# S7CAS-PLEIADES-CARTE-MERE_P02_DDR3.net
KiCad netlist of a schematic drawn in Altium Designer
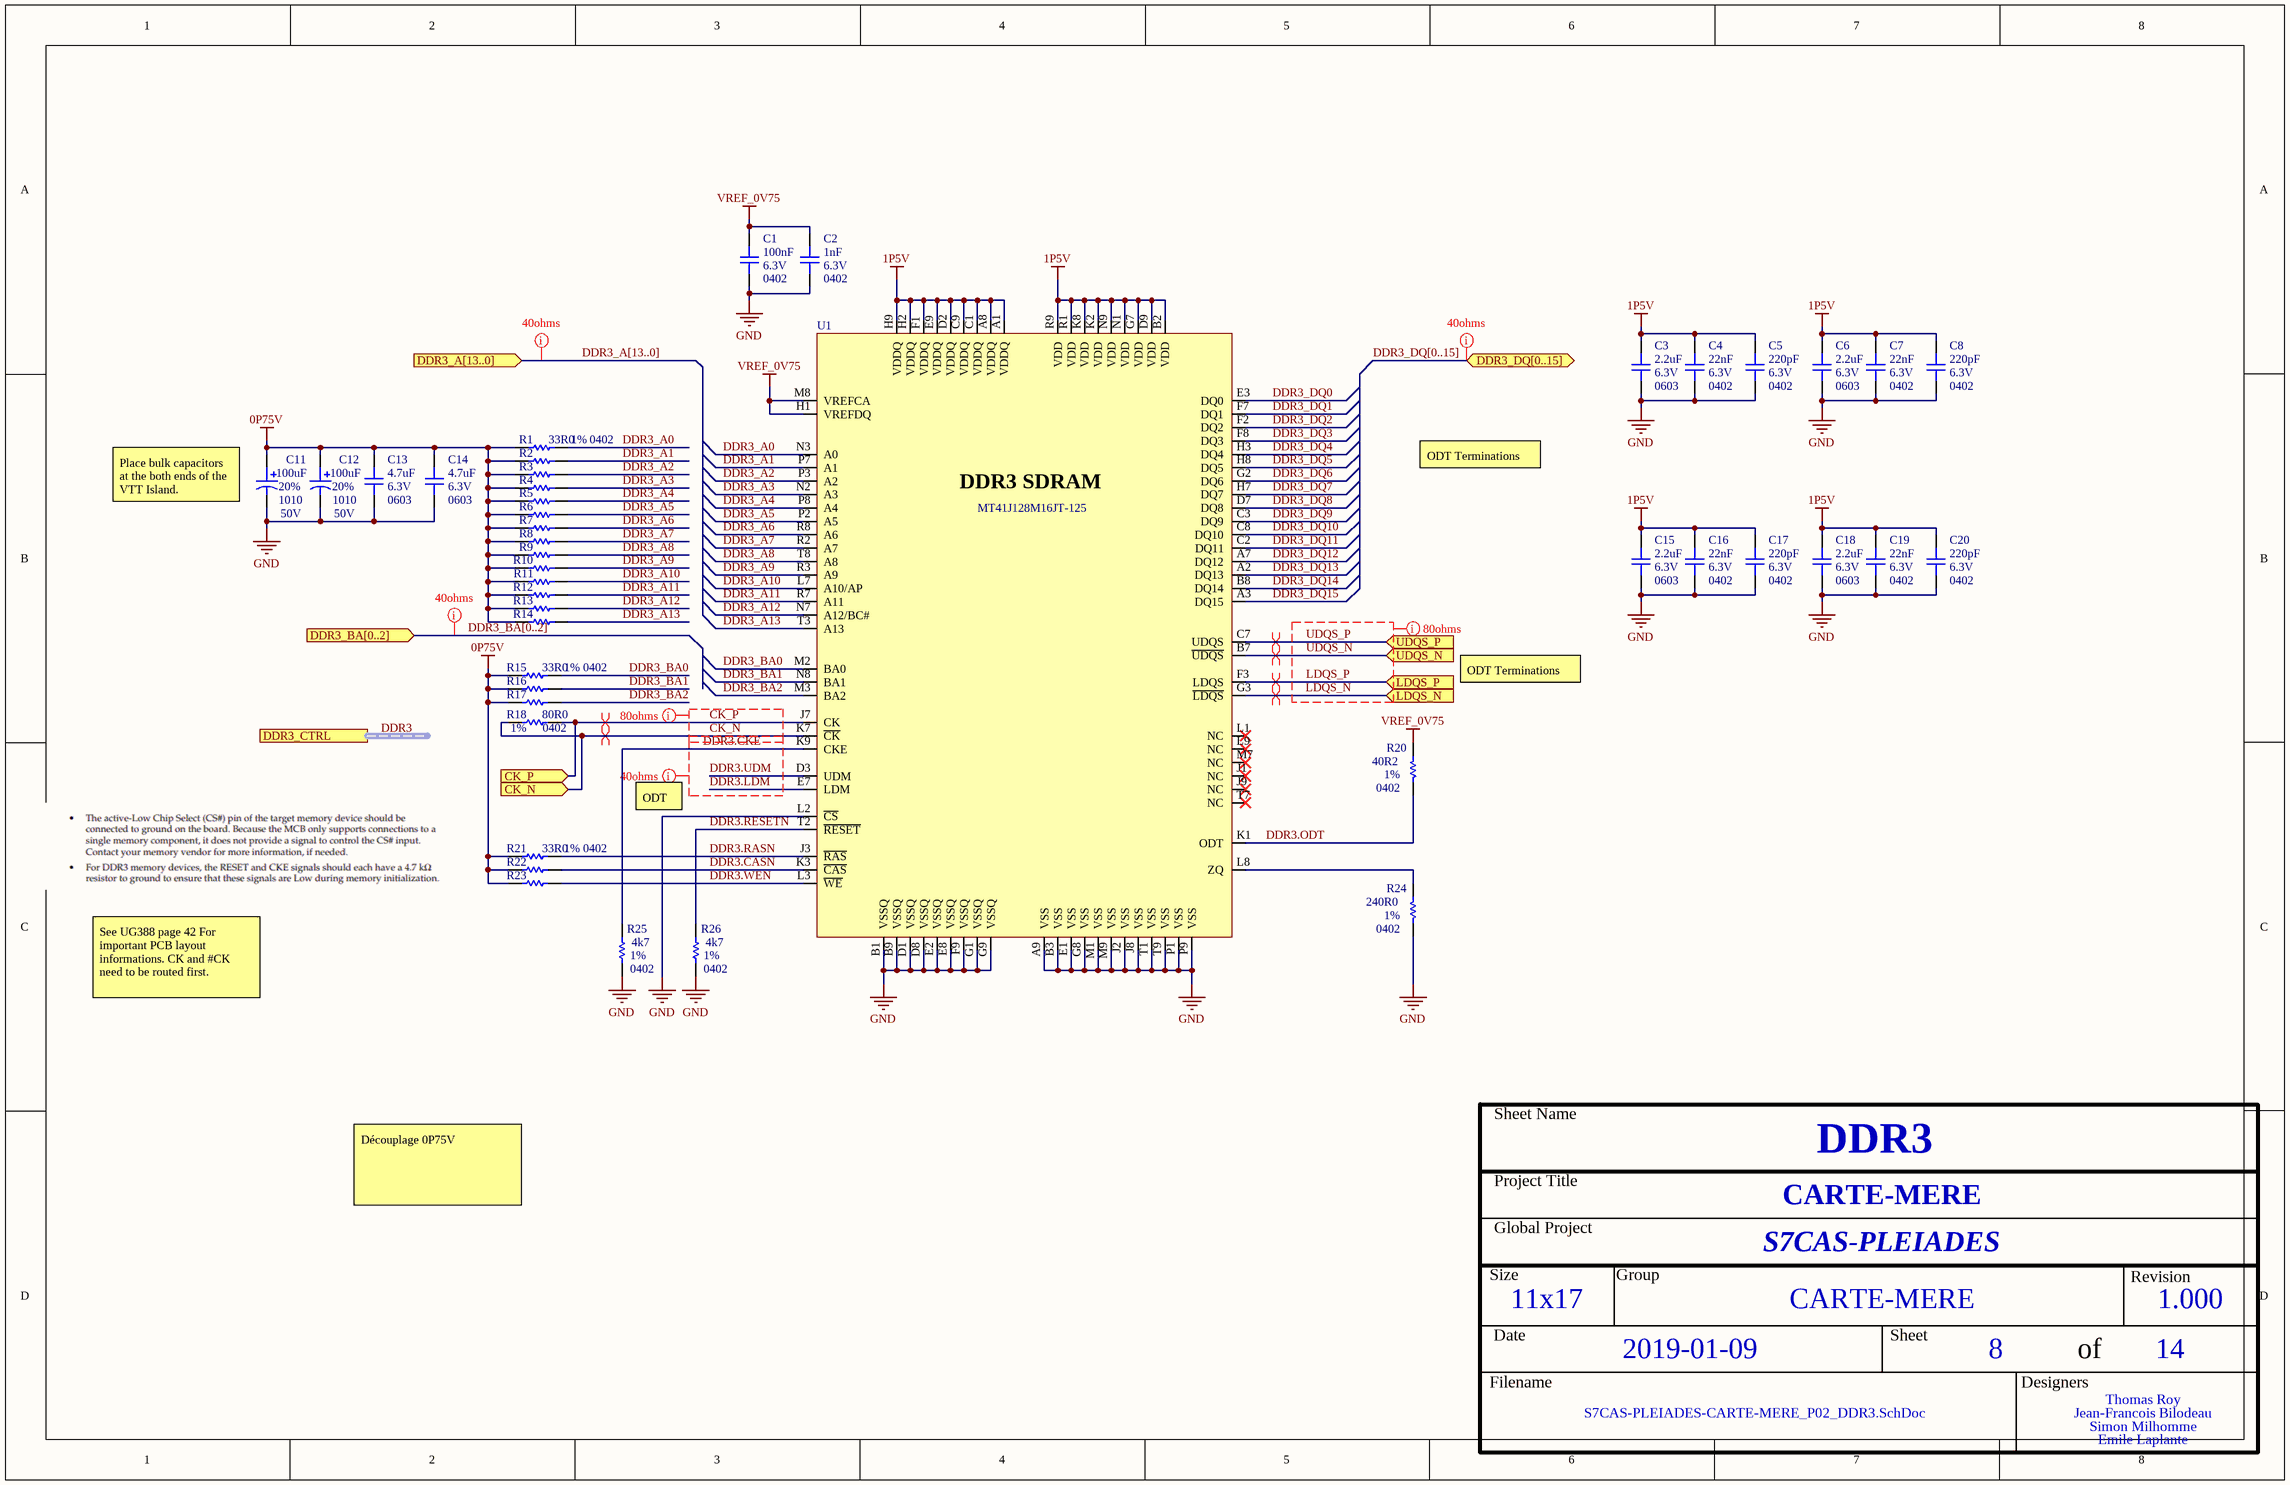
[diagram p0: S7CAS-PLEIADES-CARTE-MERE_P02_DDR3.SchDoc]

(export (version "E")
  (design (tool "Eeschema 10.0.6"))
  (components
    (comp (ref "C1")
      (value "100nF")
      (footprint "CAP_0402")
      (description "CAP - 0402")
      (fields
        (field (name "MFG") "Murata")
        (field (name "MFG PART NUMBER") "GRM022R60J104KE15")
        (field (name "VOLTAGE") "6.3V")
        (field (name "PACKAGE") "0402")
        (field (name "CREATEDBY") "Jonathan Bouchard")
      )
      (libsource (lib "S7CAS_Lib2019_REV1_00") (part "CAP - 0402"))
    )
    (comp (ref "C2")
      (value "1nF")
      (footprint "CAP_0402")
      (description "CAP - 0402")
      (fields
        (field (name "MFG") "Murata")
        (field (name "MFG PART NUMBER") "GRM022R60J104KE15")
        (field (name "VOLTAGE") "6.3V")
        (field (name "PACKAGE") "0402")
        (field (name "CREATEDBY") "Jonathan Bouchard")
      )
      (libsource (lib "S7CAS_Lib2019_REV1_00") (part "CAP - 0402"))
    )
    (comp (ref "C3")
      (value "2.2uF")
      (footprint "CAP_0603")
      (description "CAP - 0603")
      (fields
        (field (name "VOLTAGE") "6.3V")
        (field (name "PACKAGE") "0603")
        (field (name "CREATEDBY") "Jonathan Bouchard")
      )
      (libsource (lib "S7CAS_Lib2019_REV1_00") (part "CAP - 0603"))
    )
    (comp (ref "C4")
      (value "22nF")
      (footprint "CAP_0402")
      (description "CAP - 0402")
      (fields
        (field (name "MFG") "Murata")
        (field (name "MFG PART NUMBER") "GRM022R60J104KE15")
        (field (name "VOLTAGE") "6.3V")
        (field (name "PACKAGE") "0402")
        (field (name "CREATEDBY") "Jonathan Bouchard")
      )
      (libsource (lib "S7CAS_Lib2019_REV1_00") (part "CAP - 0402"))
    )
    (comp (ref "C5")
      (value "220pF")
      (footprint "CAP_0402")
      (description "CAP - 0402")
      (fields
        (field (name "MFG") "Murata")
        (field (name "MFG PART NUMBER") "GRM022R60J104KE15")
        (field (name "VOLTAGE") "6.3V")
        (field (name "PACKAGE") "0402")
        (field (name "CREATEDBY") "Jonathan Bouchard")
      )
      (libsource (lib "S7CAS_Lib2019_REV1_00") (part "CAP - 0402"))
    )
    (comp (ref "C6")
      (value "2.2uF")
      (footprint "CAP_0603")
      (description "CAP - 0603")
      (fields
        (field (name "VOLTAGE") "6.3V")
        (field (name "PACKAGE") "0603")
        (field (name "CREATEDBY") "Jonathan Bouchard")
      )
      (libsource (lib "S7CAS_Lib2019_REV1_00") (part "CAP - 0603"))
    )
    (comp (ref "C7")
      (value "22nF")
      (footprint "CAP_0402")
      (description "CAP - 0402")
      (fields
        (field (name "MFG") "Murata")
        (field (name "MFG PART NUMBER") "GRM022R60J104KE15")
        (field (name "VOLTAGE") "6.3V")
        (field (name "PACKAGE") "0402")
        (field (name "CREATEDBY") "Jonathan Bouchard")
      )
      (libsource (lib "S7CAS_Lib2019_REV1_00") (part "CAP - 0402"))
    )
    (comp (ref "C8")
      (value "220pF")
      (footprint "CAP_0402")
      (description "CAP - 0402")
      (fields
        (field (name "MFG") "Murata")
        (field (name "MFG PART NUMBER") "GRM022R60J104KE15")
        (field (name "VOLTAGE") "6.3V")
        (field (name "PACKAGE") "0402")
        (field (name "CREATEDBY") "Jonathan Bouchard")
      )
      (libsource (lib "S7CAS_Lib2019_REV1_00") (part "CAP - 0402"))
    )
    (comp (ref "C11")
      (value "100uF")
      (footprint "CAP_ALU_1010_vishay")
      (description "CAP - ALU 100uF 20% 50V - 1010")
      (fields
        (field (name "MFG") "Vishay Dale")
        (field (name "MFG PART NUMBER") "MAL215099101E3")
        (field (name "VOLTAGE") "50V")
        (field (name "PACKAGE") "1010")
        (field (name "PRECISION") "20%")
        (field (name "CREATEDBY") "Jonathan Bouchard")
      )
      (libsource (lib "S7CAS_Lib2019_REV1_00") (part "CAP_ALU_MAL215099101E3"))
    )
    (comp (ref "C12")
      (value "100uF")
      (footprint "CAP_ALU_1010_vishay")
      (description "CAP - ALU 100uF 20% 50V - 1010")
      (fields
        (field (name "MFG") "Vishay Dale")
        (field (name "MFG PART NUMBER") "MAL215099101E3")
        (field (name "VOLTAGE") "50V")
        (field (name "PACKAGE") "1010")
        (field (name "PRECISION") "20%")
        (field (name "CREATEDBY") "Jonathan Bouchard")
      )
      (libsource (lib "S7CAS_Lib2019_REV1_00") (part "CAP_ALU_MAL215099101E3"))
    )
    (comp (ref "C13")
      (value "4.7uF")
      (footprint "CAP_0603")
      (description "CAP - 0603")
      (fields
        (field (name "VOLTAGE") "6.3V")
        (field (name "PACKAGE") "0603")
        (field (name "CREATEDBY") "Jonathan Bouchard")
      )
      (libsource (lib "S7CAS_Lib2019_REV1_00") (part "CAP - 0603"))
    )
    (comp (ref "C14")
      (value "4.7uF")
      (footprint "CAP_0603")
      (description "CAP - 0603")
      (fields
        (field (name "VOLTAGE") "6.3V")
        (field (name "PACKAGE") "0603")
        (field (name "CREATEDBY") "Jonathan Bouchard")
      )
      (libsource (lib "S7CAS_Lib2019_REV1_00") (part "CAP - 0603"))
    )
    (comp (ref "C15")
      (value "2.2uF")
      (footprint "CAP_0603")
      (description "CAP - 0603")
      (fields
        (field (name "VOLTAGE") "6.3V")
        (field (name "PACKAGE") "0603")
        (field (name "CREATEDBY") "Jonathan Bouchard")
      )
      (libsource (lib "S7CAS_Lib2019_REV1_00") (part "CAP - 0603"))
    )
    (comp (ref "C16")
      (value "22nF")
      (footprint "CAP_0402")
      (description "CAP - 0402")
      (fields
        (field (name "MFG") "Murata")
        (field (name "MFG PART NUMBER") "GRM022R60J104KE15")
        (field (name "VOLTAGE") "6.3V")
        (field (name "PACKAGE") "0402")
        (field (name "CREATEDBY") "Jonathan Bouchard")
      )
      (libsource (lib "S7CAS_Lib2019_REV1_00") (part "CAP - 0402"))
    )
    (comp (ref "C17")
      (value "220pF")
      (footprint "CAP_0402")
      (description "CAP - 0402")
      (fields
        (field (name "MFG") "Murata")
        (field (name "MFG PART NUMBER") "GRM022R60J104KE15")
        (field (name "VOLTAGE") "6.3V")
        (field (name "PACKAGE") "0402")
        (field (name "CREATEDBY") "Jonathan Bouchard")
      )
      (libsource (lib "S7CAS_Lib2019_REV1_00") (part "CAP - 0402"))
    )
    (comp (ref "C18")
      (value "2.2uF")
      (footprint "CAP_0603")
      (description "CAP - 0603")
      (fields
        (field (name "VOLTAGE") "6.3V")
        (field (name "PACKAGE") "0603")
        (field (name "CREATEDBY") "Jonathan Bouchard")
      )
      (libsource (lib "S7CAS_Lib2019_REV1_00") (part "CAP - 0603"))
    )
    (comp (ref "C19")
      (value "22nF")
      (footprint "CAP_0402")
      (description "CAP - 0402")
      (fields
        (field (name "MFG") "Murata")
        (field (name "MFG PART NUMBER") "GRM022R60J104KE15")
        (field (name "VOLTAGE") "6.3V")
        (field (name "PACKAGE") "0402")
        (field (name "CREATEDBY") "Jonathan Bouchard")
      )
      (libsource (lib "S7CAS_Lib2019_REV1_00") (part "CAP - 0402"))
    )
    (comp (ref "C20")
      (value "220pF")
      (footprint "CAP_0402")
      (description "CAP - 0402")
      (fields
        (field (name "MFG") "Murata")
        (field (name "MFG PART NUMBER") "GRM022R60J104KE15")
        (field (name "VOLTAGE") "6.3V")
        (field (name "PACKAGE") "0402")
        (field (name "CREATEDBY") "Jonathan Bouchard")
      )
      (libsource (lib "S7CAS_Lib2019_REV1_00") (part "CAP - 0402"))
    )
    (comp (ref "R1")
      (value "33R0")
      (footprint "RES_0402")
      (description "RES - 0402")
      (fields
        (field (name "VOLTAGE") "50V")
        (field (name "POWER") "1/16W")
        (field (name "PACKAGE") "0402")
        (field (name "PRECISION") "1%")
        (field (name "CREATEDBY") "Jonathan Bouchard")
      )
      (libsource (lib "S7CAS_Lib2019_REV1_00") (part "RES - 0402"))
    )
    (comp (ref "R2")
      (value "RES - 0402")
      (footprint "RES_0402")
      (fields
        (field (name "VOLTAGE") "50V")
        (field (name "POWER") "1/16W")
        (field (name "CREATEDBY") "Jonathan Bouchard")
      )
      (libsource (lib "S7CAS_Lib2019_REV1_00") (part "RES - 0402"))
    )
    (comp (ref "R3")
      (value "RES - 0402")
      (footprint "RES_0402")
      (fields
        (field (name "VOLTAGE") "50V")
        (field (name "POWER") "1/16W")
        (field (name "CREATEDBY") "Jonathan Bouchard")
      )
      (libsource (lib "S7CAS_Lib2019_REV1_00") (part "RES - 0402"))
    )
    (comp (ref "R4")
      (value "RES - 0402")
      (footprint "RES_0402")
      (fields
        (field (name "VOLTAGE") "50V")
        (field (name "POWER") "1/16W")
        (field (name "CREATEDBY") "Jonathan Bouchard")
      )
      (libsource (lib "S7CAS_Lib2019_REV1_00") (part "RES - 0402"))
    )
    (comp (ref "R5")
      (value "RES - 0402")
      (footprint "RES_0402")
      (fields
        (field (name "VOLTAGE") "50V")
        (field (name "POWER") "1/16W")
        (field (name "CREATEDBY") "Jonathan Bouchard")
      )
      (libsource (lib "S7CAS_Lib2019_REV1_00") (part "RES - 0402"))
    )
    (comp (ref "R6")
      (value "RES - 0402")
      (footprint "RES_0402")
      (fields
        (field (name "VOLTAGE") "50V")
        (field (name "POWER") "1/16W")
        (field (name "CREATEDBY") "Jonathan Bouchard")
      )
      (libsource (lib "S7CAS_Lib2019_REV1_00") (part "RES - 0402"))
    )
    (comp (ref "R7")
      (value "RES - 0402")
      (footprint "RES_0402")
      (fields
        (field (name "VOLTAGE") "50V")
        (field (name "POWER") "1/16W")
        (field (name "CREATEDBY") "Jonathan Bouchard")
      )
      (libsource (lib "S7CAS_Lib2019_REV1_00") (part "RES - 0402"))
    )
    (comp (ref "R8")
      (value "RES - 0402")
      (footprint "RES_0402")
      (fields
        (field (name "VOLTAGE") "50V")
        (field (name "POWER") "1/16W")
        (field (name "CREATEDBY") "Jonathan Bouchard")
      )
      (libsource (lib "S7CAS_Lib2019_REV1_00") (part "RES - 0402"))
    )
    (comp (ref "R9")
      (value "RES - 0402")
      (footprint "RES_0402")
      (fields
        (field (name "VOLTAGE") "50V")
        (field (name "POWER") "1/16W")
        (field (name "CREATEDBY") "Jonathan Bouchard")
      )
      (libsource (lib "S7CAS_Lib2019_REV1_00") (part "RES - 0402"))
    )
    (comp (ref "R10")
      (value "RES - 0402")
      (footprint "RES_0402")
      (fields
        (field (name "VOLTAGE") "50V")
        (field (name "POWER") "1/16W")
        (field (name "CREATEDBY") "Jonathan Bouchard")
      )
      (libsource (lib "S7CAS_Lib2019_REV1_00") (part "RES - 0402"))
    )
    (comp (ref "R11")
      (value "RES - 0402")
      (footprint "RES_0402")
      (fields
        (field (name "VOLTAGE") "50V")
        (field (name "POWER") "1/16W")
        (field (name "CREATEDBY") "Jonathan Bouchard")
      )
      (libsource (lib "S7CAS_Lib2019_REV1_00") (part "RES - 0402"))
    )
    (comp (ref "R12")
      (value "RES - 0402")
      (footprint "RES_0402")
      (fields
        (field (name "VOLTAGE") "50V")
        (field (name "POWER") "1/16W")
        (field (name "CREATEDBY") "Jonathan Bouchard")
      )
      (libsource (lib "S7CAS_Lib2019_REV1_00") (part "RES - 0402"))
    )
    (comp (ref "R13")
      (value "RES - 0402")
      (footprint "RES_0402")
      (fields
        (field (name "VOLTAGE") "50V")
        (field (name "POWER") "1/16W")
        (field (name "CREATEDBY") "Jonathan Bouchard")
      )
      (libsource (lib "S7CAS_Lib2019_REV1_00") (part "RES - 0402"))
    )
    (comp (ref "R14")
      (value "RES - 0402")
      (footprint "RES_0402")
      (fields
        (field (name "VOLTAGE") "50V")
        (field (name "POWER") "1/16W")
        (field (name "CREATEDBY") "Jonathan Bouchard")
      )
      (libsource (lib "S7CAS_Lib2019_REV1_00") (part "RES - 0402"))
    )
    (comp (ref "R15")
      (value "33R0")
      (footprint "RES_0402")
      (description "RES - 0402")
      (fields
        (field (name "VOLTAGE") "50V")
        (field (name "POWER") "1/16W")
        (field (name "PACKAGE") "0402")
        (field (name "PRECISION") "1%")
        (field (name "CREATEDBY") "Jonathan Bouchard")
      )
      (libsource (lib "S7CAS_Lib2019_REV1_00") (part "RES - 0402"))
    )
    (comp (ref "R16")
      (value "RES - 0402")
      (footprint "RES_0402")
      (fields
        (field (name "VOLTAGE") "50V")
        (field (name "POWER") "1/16W")
        (field (name "CREATEDBY") "Jonathan Bouchard")
      )
      (libsource (lib "S7CAS_Lib2019_REV1_00") (part "RES - 0402"))
    )
    (comp (ref "R17")
      (value "RES - 0402")
      (footprint "RES_0402")
      (fields
        (field (name "VOLTAGE") "50V")
        (field (name "POWER") "1/16W")
        (field (name "CREATEDBY") "Jonathan Bouchard")
      )
      (libsource (lib "S7CAS_Lib2019_REV1_00") (part "RES - 0402"))
    )
    (comp (ref "R18")
      (value "80R0")
      (footprint "RES_0402")
      (description "RES - 0402")
      (fields
        (field (name "VOLTAGE") "50V")
        (field (name "POWER") "1/16W")
        (field (name "PACKAGE") "0402")
        (field (name "PRECISION") "1%")
        (field (name "CREATEDBY") "Jonathan Bouchard")
      )
      (libsource (lib "S7CAS_Lib2019_REV1_00") (part "RES - 0402"))
    )
    (comp (ref "R20")
      (value "40R2")
      (footprint "RES_0402")
      (description "RES - 0402")
      (fields
        (field (name "VOLTAGE") "50V")
        (field (name "POWER") "1/16W")
        (field (name "PACKAGE") "0402")
        (field (name "PRECISION") "1%")
        (field (name "CREATEDBY") "Jonathan Bouchard")
      )
      (libsource (lib "S7CAS_Lib2019_REV1_00") (part "RES - 0402"))
    )
    (comp (ref "R21")
      (value "33R0")
      (footprint "RES_0402")
      (description "RES - 0402")
      (fields
        (field (name "VOLTAGE") "50V")
        (field (name "POWER") "1/16W")
        (field (name "PACKAGE") "0402")
        (field (name "PRECISION") "1%")
        (field (name "CREATEDBY") "Jonathan Bouchard")
      )
      (libsource (lib "S7CAS_Lib2019_REV1_00") (part "RES - 0402"))
    )
    (comp (ref "R22")
      (value "RES - 0402")
      (footprint "RES_0402")
      (fields
        (field (name "VOLTAGE") "50V")
        (field (name "POWER") "1/16W")
        (field (name "CREATEDBY") "Jonathan Bouchard")
      )
      (libsource (lib "S7CAS_Lib2019_REV1_00") (part "RES - 0402"))
    )
    (comp (ref "R23")
      (value "RES - 0402")
      (footprint "RES_0402")
      (fields
        (field (name "VOLTAGE") "50V")
        (field (name "POWER") "1/16W")
        (field (name "CREATEDBY") "Jonathan Bouchard")
      )
      (libsource (lib "S7CAS_Lib2019_REV1_00") (part "RES - 0402"))
    )
    (comp (ref "R24")
      (value "240R0")
      (footprint "RES_0402")
      (description "RES - 0402")
      (fields
        (field (name "VOLTAGE") "50V")
        (field (name "POWER") "1/16W")
        (field (name "PACKAGE") "0402")
        (field (name "PRECISION") "1%")
        (field (name "CREATEDBY") "Jonathan Bouchard")
      )
      (libsource (lib "S7CAS_Lib2019_REV1_00") (part "RES - 0402"))
    )
    (comp (ref "R25")
      (value "4k7")
      (footprint "RES_0402")
      (description "RES - 0402")
      (fields
        (field (name "VOLTAGE") "50V")
        (field (name "POWER") "1/16W")
        (field (name "PACKAGE") "0402")
        (field (name "PRECISION") "1%")
        (field (name "CREATEDBY") "Jonathan Bouchard")
      )
      (libsource (lib "S7CAS_Lib2019_REV1_00") (part "RES - 0402"))
    )
    (comp (ref "R26")
      (value "4k7")
      (footprint "RES_0402")
      (description "RES - 0402")
      (fields
        (field (name "VOLTAGE") "50V")
        (field (name "POWER") "1/16W")
        (field (name "PACKAGE") "0402")
        (field (name "PRECISION") "1%")
        (field (name "CREATEDBY") "Jonathan Bouchard")
      )
      (libsource (lib "S7CAS_Lib2019_REV1_00") (part "RES - 0402"))
    )
    (comp (ref "U1")
      (value "MT41J128M16JT-125")
      (footprint "MEM_DDR3_MT41J128M16JT-125")
      (description "MEM - DDR3 SDRAM 2GBIT 800MHZ - TFBGA-96")
      (fields
        (field (name "VOLTAGE") "1.425 V ~ 1.575 V")
        (field (name "MFG") "Micrel")
        (field (name "CREATEDBY") "Jonathan Bouchard")
      )
      (libsource (lib "S7CAS_Lib2019_REV1_00") (part "MEM_DDR3_MT41J128M16JT-125{colon}K TR"))
    )
  )
  (nets
    (net (code "2") (name "/CK_N") (class "Default")
      (node (ref "R18") (pin "2") (pinfunction "2_2") (pintype "passive"))
      (node (ref "U1") (pin "K7") (pinfunction "CK_K7") (pintype "passive"))
    )
    (net (code "3") (name "/CK_P") (class "Default")
      (node (ref "R18") (pin "1") (pinfunction "1_1") (pintype "passive"))
      (node (ref "U1") (pin "J7") (pinfunction "CK_J7") (pintype "passive"))
    )
    (net (code "4") (name "/DDR3.CASN") (class "Default")
      (node (ref "R22") (pin "1") (pinfunction "1_1") (pintype "passive"))
      (node (ref "U1") (pin "K3") (pinfunction "CAS_K3") (pintype "passive"))
    )
    (net (code "5") (name "/DDR3.CKE") (class "Default")
      (node (ref "R25") (pin "2") (pinfunction "2_2") (pintype "passive"))
      (node (ref "U1") (pin "K9") (pinfunction "CKE_K9") (pintype "passive"))
    )
    (net (code "6") (name "/DDR3.LDM") (class "Default")
      (node (ref "U1") (pin "E7") (pinfunction "LDM_E7") (pintype "power_in"))
    )
    (net (code "7") (name "/DDR3.ODT") (class "Default")
      (node (ref "R20") (pin "1") (pinfunction "1_1") (pintype "passive"))
      (node (ref "U1") (pin "K1") (pinfunction "ODT_K1") (pintype "passive"))
    )
    (net (code "8") (name "/DDR3.RASN") (class "Default")
      (node (ref "R21") (pin "1") (pinfunction "1_1") (pintype "passive"))
      (node (ref "U1") (pin "J3") (pinfunction "RAS_J3") (pintype "passive"))
    )
    (net (code "9") (name "/DDR3.RESETN") (class "Default")
      (node (ref "R26") (pin "2") (pinfunction "2_2") (pintype "passive"))
      (node (ref "U1") (pin "T2") (pinfunction "RESET_T2") (pintype "passive"))
    )
    (net (code "10") (name "/DDR3.UDM") (class "Default")
      (node (ref "U1") (pin "D3") (pinfunction "UDM_D3") (pintype "power_in"))
    )
    (net (code "11") (name "/DDR3.WEN") (class "Default")
      (node (ref "R23") (pin "1") (pinfunction "1_1") (pintype "passive"))
      (node (ref "U1") (pin "L3") (pinfunction "WE_L3") (pintype "passive"))
    )
    (net (code "12") (name "/DDR3_A0") (class "Default")
      (node (ref "R1") (pin "1") (pinfunction "1_1") (pintype "passive"))
      (node (ref "U1") (pin "N3") (pinfunction "A0_N3") (pintype "passive"))
    )
    (net (code "13") (name "/DDR3_A1") (class "Default")
      (node (ref "R2") (pin "1") (pinfunction "1_1") (pintype "passive"))
      (node (ref "U1") (pin "P7") (pinfunction "A1_P7") (pintype "passive"))
    )
    (net (code "14") (name "/DDR3_A2") (class "Default")
      (node (ref "R3") (pin "1") (pinfunction "1_1") (pintype "passive"))
      (node (ref "U1") (pin "P3") (pinfunction "A2_P3") (pintype "passive"))
    )
    (net (code "15") (name "/DDR3_A3") (class "Default")
      (node (ref "R4") (pin "1") (pinfunction "1_1") (pintype "passive"))
      (node (ref "U1") (pin "N2") (pinfunction "A3_N2") (pintype "passive"))
    )
    (net (code "16") (name "/DDR3_A4") (class "Default")
      (node (ref "R5") (pin "1") (pinfunction "1_1") (pintype "passive"))
      (node (ref "U1") (pin "P8") (pinfunction "A4_P8") (pintype "passive"))
    )
    (net (code "17") (name "/DDR3_A5") (class "Default")
      (node (ref "R6") (pin "1") (pinfunction "1_1") (pintype "passive"))
      (node (ref "U1") (pin "P2") (pinfunction "A5_P2") (pintype "passive"))
    )
    (net (code "18") (name "/DDR3_A6") (class "Default")
      (node (ref "R7") (pin "1") (pinfunction "1_1") (pintype "passive"))
      (node (ref "U1") (pin "R8") (pinfunction "A6_R8") (pintype "passive"))
    )
    (net (code "19") (name "/DDR3_A7") (class "Default")
      (node (ref "R8") (pin "1") (pinfunction "1_1") (pintype "passive"))
      (node (ref "U1") (pin "R2") (pinfunction "A7_R2") (pintype "passive"))
    )
    (net (code "20") (name "/DDR3_A8") (class "Default")
      (node (ref "R9") (pin "1") (pinfunction "1_1") (pintype "passive"))
      (node (ref "U1") (pin "T8") (pinfunction "A8_T8") (pintype "passive"))
    )
    (net (code "21") (name "/DDR3_A9") (class "Default")
      (node (ref "R10") (pin "1") (pinfunction "1_1") (pintype "passive"))
      (node (ref "U1") (pin "R3") (pinfunction "A9_R3") (pintype "passive"))
    )
    (net (code "22") (name "/DDR3_A10") (class "Default")
      (node (ref "R11") (pin "1") (pinfunction "1_1") (pintype "passive"))
      (node (ref "U1") (pin "L7") (pinfunction "A10/AP_L7") (pintype "passive"))
    )
    (net (code "23") (name "/DDR3_A11") (class "Default")
      (node (ref "R12") (pin "1") (pinfunction "1_1") (pintype "passive"))
      (node (ref "U1") (pin "R7") (pinfunction "A11_R7") (pintype "passive"))
    )
    (net (code "24") (name "/DDR3_A12") (class "Default")
      (node (ref "R13") (pin "1") (pinfunction "1_1") (pintype "passive"))
      (node (ref "U1") (pin "N7") (pinfunction "A12/BC#_N7") (pintype "passive"))
    )
    (net (code "25") (name "/DDR3_A13") (class "Default")
      (node (ref "R14") (pin "1") (pinfunction "1_1") (pintype "passive"))
      (node (ref "U1") (pin "T3") (pinfunction "A13_T3") (pintype "passive"))
    )
    (net (code "27") (name "/DDR3_BA0") (class "Default")
      (node (ref "R15") (pin "1") (pinfunction "1_1") (pintype "passive"))
      (node (ref "U1") (pin "M2") (pinfunction "BA0_M2") (pintype "passive"))
    )
    (net (code "28") (name "/DDR3_BA1") (class "Default")
      (node (ref "R16") (pin "1") (pinfunction "1_1") (pintype "passive"))
      (node (ref "U1") (pin "N8") (pinfunction "BA1_N8") (pintype "passive"))
    )
    (net (code "29") (name "/DDR3_BA2") (class "Default")
      (node (ref "R17") (pin "1") (pinfunction "1_1") (pintype "passive"))
      (node (ref "U1") (pin "M3") (pinfunction "BA2_M3") (pintype "passive"))
    )
    (net (code "31") (name "/DDR3_DQ0") (class "Default")
      (node (ref "U1") (pin "E3") (pinfunction "DQ0_E3") (pintype "passive"))
    )
    (net (code "32") (name "/DDR3_DQ1") (class "Default")
      (node (ref "U1") (pin "F7") (pinfunction "DQ1_F7") (pintype "passive"))
    )
    (net (code "33") (name "/DDR3_DQ2") (class "Default")
      (node (ref "U1") (pin "F2") (pinfunction "DQ2_F2") (pintype "passive"))
    )
    (net (code "34") (name "/DDR3_DQ3") (class "Default")
      (node (ref "U1") (pin "F8") (pinfunction "DQ3_F8") (pintype "passive"))
    )
    (net (code "35") (name "/DDR3_DQ4") (class "Default")
      (node (ref "U1") (pin "H3") (pinfunction "DQ4_H3") (pintype "passive"))
    )
    (net (code "36") (name "/DDR3_DQ5") (class "Default")
      (node (ref "U1") (pin "H8") (pinfunction "DQ5_H8") (pintype "passive"))
    )
    (net (code "37") (name "/DDR3_DQ6") (class "Default")
      (node (ref "U1") (pin "G2") (pinfunction "DQ6_G2") (pintype "passive"))
    )
    (net (code "38") (name "/DDR3_DQ7") (class "Default")
      (node (ref "U1") (pin "H7") (pinfunction "DQ7_H7") (pintype "passive"))
    )
    (net (code "39") (name "/DDR3_DQ8") (class "Default")
      (node (ref "U1") (pin "D7") (pinfunction "DQ8_D7") (pintype "passive"))
    )
    (net (code "40") (name "/DDR3_DQ9") (class "Default")
      (node (ref "U1") (pin "C3") (pinfunction "DQ9_C3") (pintype "passive"))
    )
    (net (code "41") (name "/DDR3_DQ10") (class "Default")
      (node (ref "U1") (pin "C8") (pinfunction "DQ10_C8") (pintype "passive"))
    )
    (net (code "42") (name "/DDR3_DQ11") (class "Default")
      (node (ref "U1") (pin "C2") (pinfunction "DQ11_C2") (pintype "passive"))
    )
    (net (code "43") (name "/DDR3_DQ12") (class "Default")
      (node (ref "U1") (pin "A7") (pinfunction "DQ12_A7") (pintype "passive"))
    )
    (net (code "44") (name "/DDR3_DQ13") (class "Default")
      (node (ref "U1") (pin "A2") (pinfunction "DQ13_A2") (pintype "passive"))
    )
    (net (code "45") (name "/DDR3_DQ14") (class "Default")
      (node (ref "U1") (pin "B8") (pinfunction "DQ14_B8") (pintype "passive"))
    )
    (net (code "46") (name "/DDR3_DQ15") (class "Default")
      (node (ref "U1") (pin "A3") (pinfunction "DQ15_A3") (pintype "passive"))
    )
    (net (code "48") (name "/LDQS_N") (class "Default")
      (node (ref "U1") (pin "G3") (pinfunction "LDQS_G3") (pintype "passive"))
    )
    (net (code "49") (name "/LDQS_P") (class "Default")
      (node (ref "U1") (pin "F3") (pinfunction "LDQS_F3") (pintype "passive"))
    )
    (net (code "50") (name "/UDQS_N") (class "Default")
      (node (ref "U1") (pin "B7") (pinfunction "UDQS_B7") (pintype "passive"))
    )
    (net (code "51") (name "/UDQS_P") (class "Default")
      (node (ref "U1") (pin "C7") (pinfunction "UDQS_C7") (pintype "passive"))
    )
    (net (code "53") (name "0P75V") (class "Default")
      (node (ref "C11") (pin "1") (pinfunction "1_1") (pintype "passive"))
      (node (ref "C12") (pin "1") (pinfunction "1_1") (pintype "passive"))
      (node (ref "C13") (pin "2") (pinfunction "2_2") (pintype "passive"))
      (node (ref "C14") (pin "2") (pinfunction "2_2") (pintype "passive"))
      (node (ref "R1") (pin "2") (pinfunction "2_2") (pintype "passive"))
      (node (ref "R10") (pin "2") (pinfunction "2_2") (pintype "passive"))
      (node (ref "R11") (pin "2") (pinfunction "2_2") (pintype "passive"))
      (node (ref "R12") (pin "2") (pinfunction "2_2") (pintype "passive"))
      (node (ref "R13") (pin "2") (pinfunction "2_2") (pintype "passive"))
      (node (ref "R14") (pin "2") (pinfunction "2_2") (pintype "passive"))
      (node (ref "R15") (pin "2") (pinfunction "2_2") (pintype "passive"))
      (node (ref "R16") (pin "2") (pinfunction "2_2") (pintype "passive"))
      (node (ref "R17") (pin "2") (pinfunction "2_2") (pintype "passive"))
      (node (ref "R2") (pin "2") (pinfunction "2_2") (pintype "passive"))
      (node (ref "R21") (pin "2") (pinfunction "2_2") (pintype "passive"))
      (node (ref "R22") (pin "2") (pinfunction "2_2") (pintype "passive"))
      (node (ref "R23") (pin "2") (pinfunction "2_2") (pintype "passive"))
      (node (ref "R3") (pin "2") (pinfunction "2_2") (pintype "passive"))
      (node (ref "R4") (pin "2") (pinfunction "2_2") (pintype "passive"))
      (node (ref "R5") (pin "2") (pinfunction "2_2") (pintype "passive"))
      (node (ref "R6") (pin "2") (pinfunction "2_2") (pintype "passive"))
      (node (ref "R7") (pin "2") (pinfunction "2_2") (pintype "passive"))
      (node (ref "R8") (pin "2") (pinfunction "2_2") (pintype "passive"))
      (node (ref "R9") (pin "2") (pinfunction "2_2") (pintype "passive"))
    )
    (net (code "54") (name "1P5V") (class "Default")
      (node (ref "C15") (pin "2") (pinfunction "2_2") (pintype "passive"))
      (node (ref "C16") (pin "2") (pinfunction "2_2") (pintype "passive"))
      (node (ref "C17") (pin "2") (pinfunction "2_2") (pintype "passive"))
      (node (ref "C18") (pin "2") (pinfunction "2_2") (pintype "passive"))
      (node (ref "C19") (pin "2") (pinfunction "2_2") (pintype "passive"))
      (node (ref "C20") (pin "2") (pinfunction "2_2") (pintype "passive"))
      (node (ref "C3") (pin "2") (pinfunction "2_2") (pintype "passive"))
      (node (ref "C4") (pin "2") (pinfunction "2_2") (pintype "passive"))
      (node (ref "C5") (pin "2") (pinfunction "2_2") (pintype "passive"))
      (node (ref "C6") (pin "2") (pinfunction "2_2") (pintype "passive"))
      (node (ref "C7") (pin "2") (pinfunction "2_2") (pintype "passive"))
      (node (ref "C8") (pin "2") (pinfunction "2_2") (pintype "passive"))
      (node (ref "U1") (pin "A1") (pinfunction "VDDQ_A1") (pintype "power_in"))
      (node (ref "U1") (pin "A8") (pinfunction "VDDQ_A8") (pintype "power_in"))
      (node (ref "U1") (pin "B2") (pinfunction "VDD_B2") (pintype "power_in"))
      (node (ref "U1") (pin "C1") (pinfunction "VDDQ_C1") (pintype "power_in"))
      (node (ref "U1") (pin "C9") (pinfunction "VDDQ_C9") (pintype "power_in"))
      (node (ref "U1") (pin "D2") (pinfunction "VDDQ_D2") (pintype "power_in"))
      (node (ref "U1") (pin "D9") (pinfunction "VDD_D9") (pintype "power_in"))
      (node (ref "U1") (pin "E9") (pinfunction "VDDQ_E9") (pintype "power_in"))
      (node (ref "U1") (pin "F1") (pinfunction "VDDQ_F1") (pintype "power_in"))
      (node (ref "U1") (pin "G7") (pinfunction "VDD_G7") (pintype "power_in"))
      (node (ref "U1") (pin "H2") (pinfunction "VDDQ_H2") (pintype "power_in"))
      (node (ref "U1") (pin "H9") (pinfunction "VDDQ_H9") (pintype "power_in"))
      (node (ref "U1") (pin "K2") (pinfunction "VDD_K2") (pintype "power_in"))
      (node (ref "U1") (pin "K8") (pinfunction "VDD_K8") (pintype "power_in"))
      (node (ref "U1") (pin "N1") (pinfunction "VDD_N1") (pintype "power_in"))
      (node (ref "U1") (pin "N9") (pinfunction "VDD_N9") (pintype "power_in"))
      (node (ref "U1") (pin "R1") (pinfunction "VDD_R1") (pintype "power_in"))
      (node (ref "U1") (pin "R9") (pinfunction "VDD_R9") (pintype "power_in"))
    )
    (net (code "55") (name "GND") (class "Default")
      (node (ref "C1") (pin "1") (pinfunction "1_1") (pintype "passive"))
      (node (ref "C11") (pin "2") (pinfunction "2_2") (pintype "passive"))
      (node (ref "C12") (pin "2") (pinfunction "2_2") (pintype "passive"))
      (node (ref "C13") (pin "1") (pinfunction "1_1") (pintype "passive"))
      (node (ref "C14") (pin "1") (pinfunction "1_1") (pintype "passive"))
      (node (ref "C15") (pin "1") (pinfunction "1_1") (pintype "passive"))
      (node (ref "C16") (pin "1") (pinfunction "1_1") (pintype "passive"))
      (node (ref "C17") (pin "1") (pinfunction "1_1") (pintype "passive"))
      (node (ref "C18") (pin "1") (pinfunction "1_1") (pintype "passive"))
      (node (ref "C19") (pin "1") (pinfunction "1_1") (pintype "passive"))
      (node (ref "C2") (pin "1") (pinfunction "1_1") (pintype "passive"))
      (node (ref "C20") (pin "1") (pinfunction "1_1") (pintype "passive"))
      (node (ref "C3") (pin "1") (pinfunction "1_1") (pintype "passive"))
      (node (ref "C4") (pin "1") (pinfunction "1_1") (pintype "passive"))
      (node (ref "C5") (pin "1") (pinfunction "1_1") (pintype "passive"))
      (node (ref "C6") (pin "1") (pinfunction "1_1") (pintype "passive"))
      (node (ref "C7") (pin "1") (pinfunction "1_1") (pintype "passive"))
      (node (ref "C8") (pin "1") (pinfunction "1_1") (pintype "passive"))
      (node (ref "R24") (pin "1") (pinfunction "1_1") (pintype "passive"))
      (node (ref "R25") (pin "1") (pinfunction "1_1") (pintype "passive"))
      (node (ref "R26") (pin "1") (pinfunction "1_1") (pintype "passive"))
      (node (ref "U1") (pin "A9") (pinfunction "VSS_A9") (pintype "passive"))
      (node (ref "U1") (pin "B1") (pinfunction "VSSQ_B1") (pintype "passive"))
      (node (ref "U1") (pin "B3") (pinfunction "VSS_B3") (pintype "passive"))
      (node (ref "U1") (pin "B9") (pinfunction "VSSQ_B9") (pintype "passive"))
      (node (ref "U1") (pin "D1") (pinfunction "VSSQ_D1") (pintype "passive"))
      (node (ref "U1") (pin "D8") (pinfunction "VSSQ_D8") (pintype "passive"))
      (node (ref "U1") (pin "E1") (pinfunction "VSS_E1") (pintype "passive"))
      (node (ref "U1") (pin "E2") (pinfunction "VSSQ_E2") (pintype "passive"))
      (node (ref "U1") (pin "E8") (pinfunction "VSSQ_E8") (pintype "passive"))
      (node (ref "U1") (pin "F9") (pinfunction "VSSQ_F9") (pintype "passive"))
      (node (ref "U1") (pin "G1") (pinfunction "VSSQ_G1") (pintype "passive"))
      (node (ref "U1") (pin "G8") (pinfunction "VSS_G8") (pintype "passive"))
      (node (ref "U1") (pin "G9") (pinfunction "VSSQ_G9") (pintype "passive"))
      (node (ref "U1") (pin "J2") (pinfunction "VSS_J2") (pintype "passive"))
      (node (ref "U1") (pin "J8") (pinfunction "VSS_J8") (pintype "passive"))
      (node (ref "U1") (pin "L2") (pinfunction "CS_L2") (pintype "passive"))
      (node (ref "U1") (pin "M1") (pinfunction "VSS_M1") (pintype "passive"))
      (node (ref "U1") (pin "M9") (pinfunction "VSS_M9") (pintype "passive"))
      (node (ref "U1") (pin "P1") (pinfunction "VSS_P1") (pintype "passive"))
      (node (ref "U1") (pin "P9") (pinfunction "VSS_P9") (pintype "passive"))
      (node (ref "U1") (pin "T1") (pinfunction "VSS_T1") (pintype "passive"))
      (node (ref "U1") (pin "T9") (pinfunction "VSS_T9") (pintype "passive"))
    )
    (net (code "56") (name "Net-(U1-ZQ)") (class "Default")
      (node (ref "R24") (pin "2") (pinfunction "2_2") (pintype "passive"))
      (node (ref "U1") (pin "L8") (pinfunction "ZQ_L8") (pintype "passive"))
    )
    (net (code "57") (name "VREF_0V75") (class "Default")
      (node (ref "C1") (pin "2") (pinfunction "2_2") (pintype "passive"))
      (node (ref "C2") (pin "2") (pinfunction "2_2") (pintype "passive"))
      (node (ref "R20") (pin "2") (pinfunction "2_2") (pintype "passive"))
      (node (ref "U1") (pin "H1") (pinfunction "VREFDQ_H1") (pintype "passive"))
      (node (ref "U1") (pin "M8") (pinfunction "VREFCA_M8") (pintype "passive"))
    )
    (net (code "58") (name "unconnected-(U1-NC-PadJ1)") (class "Default")
      (node (ref "U1") (pin "J1") (pinfunction "NC_J1") (pintype "passive+no_connect"))
    )
    (net (code "59") (name "unconnected-(U1-NC-PadJ9)") (class "Default")
      (node (ref "U1") (pin "J9") (pinfunction "NC_J9") (pintype "passive+no_connect"))
    )
    (net (code "60") (name "unconnected-(U1-NC-PadL1)") (class "Default")
      (node (ref "U1") (pin "L1") (pinfunction "NC_L1") (pintype "passive+no_connect"))
    )
    (net (code "61") (name "unconnected-(U1-NC-PadL9)") (class "Default")
      (node (ref "U1") (pin "L9") (pinfunction "NC_L9") (pintype "passive+no_connect"))
    )
    (net (code "62") (name "unconnected-(U1-NC-PadM7)") (class "Default")
      (node (ref "U1") (pin "M7") (pinfunction "NC_M7") (pintype "passive+no_connect"))
    )
    (net (code "63") (name "unconnected-(U1-NC-PadT7)") (class "Default")
      (node (ref "U1") (pin "T7") (pinfunction "NC_T7") (pintype "passive+no_connect"))
    )
  )
)
